# FPGA_mgt.net
KiCad netlist of a schematic drawn in Altium Designer
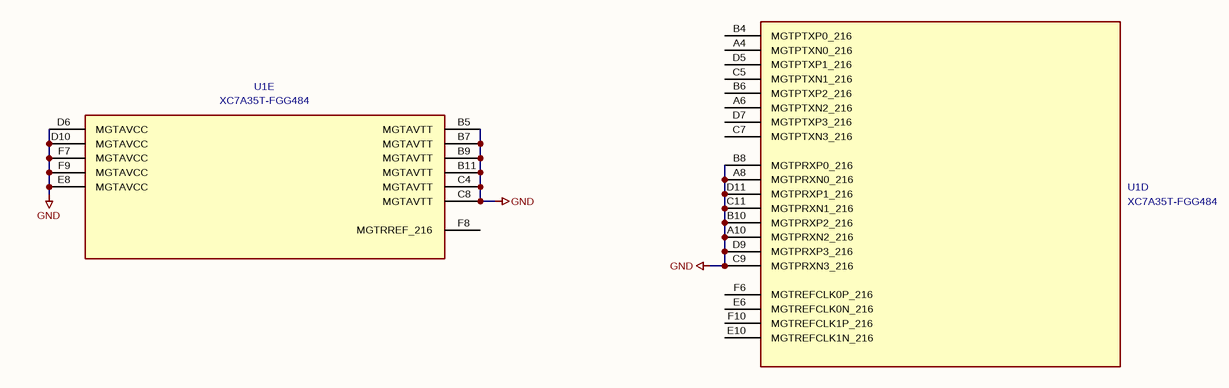
[diagram p0: FPGA_mgt.SchDoc]

(export (version "E")
  (design (tool "Eeschema 10.0.6"))
  (components
    (comp (ref "U1")
      (value "XC7A35T-FGG484")
      (footprint "FB-BGA-484_23.0x23.0mm_Layout22x22_P1.0mm")
      (libsource (lib "som_fpga") (part "XC7A35T-FGG484"))
    )
  )
  (nets
    (net (code "1") (name "GND") (class "Default")
      (node (ref "U1") (pin "A10") (pinfunction "MGTPRXN2_216_A10") (pintype "passive"))
      (node (ref "U1") (pin "A8") (pinfunction "MGTPRXN0_216_A8") (pintype "passive"))
      (node (ref "U1") (pin "B10") (pinfunction "MGTPRXP2_216_B10") (pintype "passive"))
      (node (ref "U1") (pin "B11") (pinfunction "MGTAVTT_B11") (pintype "passive"))
      (node (ref "U1") (pin "B5") (pinfunction "MGTAVTT_B5") (pintype "passive"))
      (node (ref "U1") (pin "B7") (pinfunction "MGTAVTT_B7") (pintype "passive"))
      (node (ref "U1") (pin "B8") (pinfunction "MGTPRXP0_216_B8") (pintype "passive"))
      (node (ref "U1") (pin "B9") (pinfunction "MGTAVTT_B9") (pintype "passive"))
      (node (ref "U1") (pin "C11") (pinfunction "MGTPRXN1_216_C11") (pintype "passive"))
      (node (ref "U1") (pin "C4") (pinfunction "MGTAVTT_C4") (pintype "passive"))
      (node (ref "U1") (pin "C8") (pinfunction "MGTAVTT_C8") (pintype "passive"))
      (node (ref "U1") (pin "C9") (pinfunction "MGTPRXN3_216_C9") (pintype "passive"))
      (node (ref "U1") (pin "D10") (pinfunction "MGTAVCC_D10") (pintype "passive"))
      (node (ref "U1") (pin "D11") (pinfunction "MGTPRXP1_216_D11") (pintype "passive"))
      (node (ref "U1") (pin "D6") (pinfunction "MGTAVCC_D6") (pintype "passive"))
      (node (ref "U1") (pin "D9") (pinfunction "MGTPRXP3_216_D9") (pintype "passive"))
      (node (ref "U1") (pin "E8") (pinfunction "MGTAVCC_E8") (pintype "passive"))
      (node (ref "U1") (pin "F7") (pinfunction "MGTAVCC_F7") (pintype "passive"))
      (node (ref "U1") (pin "F9") (pinfunction "MGTAVCC_F9") (pintype "passive"))
    )
    (net (code "2") (name "unconnected-(U1D-MGTPTXN0_216-PadA4)") (class "Default")
      (node (ref "U1") (pin "A4") (pinfunction "MGTPTXN0_216_A4") (pintype "passive"))
    )
    (net (code "3") (name "unconnected-(U1D-MGTPTXN1_216-PadC5)") (class "Default")
      (node (ref "U1") (pin "C5") (pinfunction "MGTPTXN1_216_C5") (pintype "passive"))
    )
    (net (code "4") (name "unconnected-(U1D-MGTPTXN2_216-PadA6)") (class "Default")
      (node (ref "U1") (pin "A6") (pinfunction "MGTPTXN2_216_A6") (pintype "passive"))
    )
    (net (code "5") (name "unconnected-(U1D-MGTPTXN3_216-PadC7)") (class "Default")
      (node (ref "U1") (pin "C7") (pinfunction "MGTPTXN3_216_C7") (pintype "passive"))
    )
    (net (code "6") (name "unconnected-(U1D-MGTPTXP0_216-PadB4)") (class "Default")
      (node (ref "U1") (pin "B4") (pinfunction "MGTPTXP0_216_B4") (pintype "passive"))
    )
    (net (code "7") (name "unconnected-(U1D-MGTPTXP1_216-PadD5)") (class "Default")
      (node (ref "U1") (pin "D5") (pinfunction "MGTPTXP1_216_D5") (pintype "passive"))
    )
    (net (code "8") (name "unconnected-(U1D-MGTPTXP2_216-PadB6)") (class "Default")
      (node (ref "U1") (pin "B6") (pinfunction "MGTPTXP2_216_B6") (pintype "passive"))
    )
    (net (code "9") (name "unconnected-(U1D-MGTPTXP3_216-PadD7)") (class "Default")
      (node (ref "U1") (pin "D7") (pinfunction "MGTPTXP3_216_D7") (pintype "passive"))
    )
    (net (code "10") (name "unconnected-(U1D-MGTREFCLK0N_216-PadE6)") (class "Default")
      (node (ref "U1") (pin "E6") (pinfunction "MGTREFCLK0N_216_E6") (pintype "passive"))
    )
    (net (code "11") (name "unconnected-(U1D-MGTREFCLK0P_216-PadF6)") (class "Default")
      (node (ref "U1") (pin "F6") (pinfunction "MGTREFCLK0P_216_F6") (pintype "passive"))
    )
    (net (code "12") (name "unconnected-(U1D-MGTREFCLK1N_216-PadE10)") (class "Default")
      (node (ref "U1") (pin "E10") (pinfunction "MGTREFCLK1N_216_E10") (pintype "passive"))
    )
    (net (code "13") (name "unconnected-(U1D-MGTREFCLK1P_216-PadF10)") (class "Default")
      (node (ref "U1") (pin "F10") (pinfunction "MGTREFCLK1P_216_F10") (pintype "passive"))
    )
    (net (code "14") (name "unconnected-(U1E-MGTRREF_216-PadF8)") (class "Default")
      (node (ref "U1") (pin "F8") (pinfunction "MGTRREF_216_F8") (pintype "passive"))
    )
  )
)
